# vestibular_vampire.net
KiCad netlist of a schematic drawn in Altium Designer
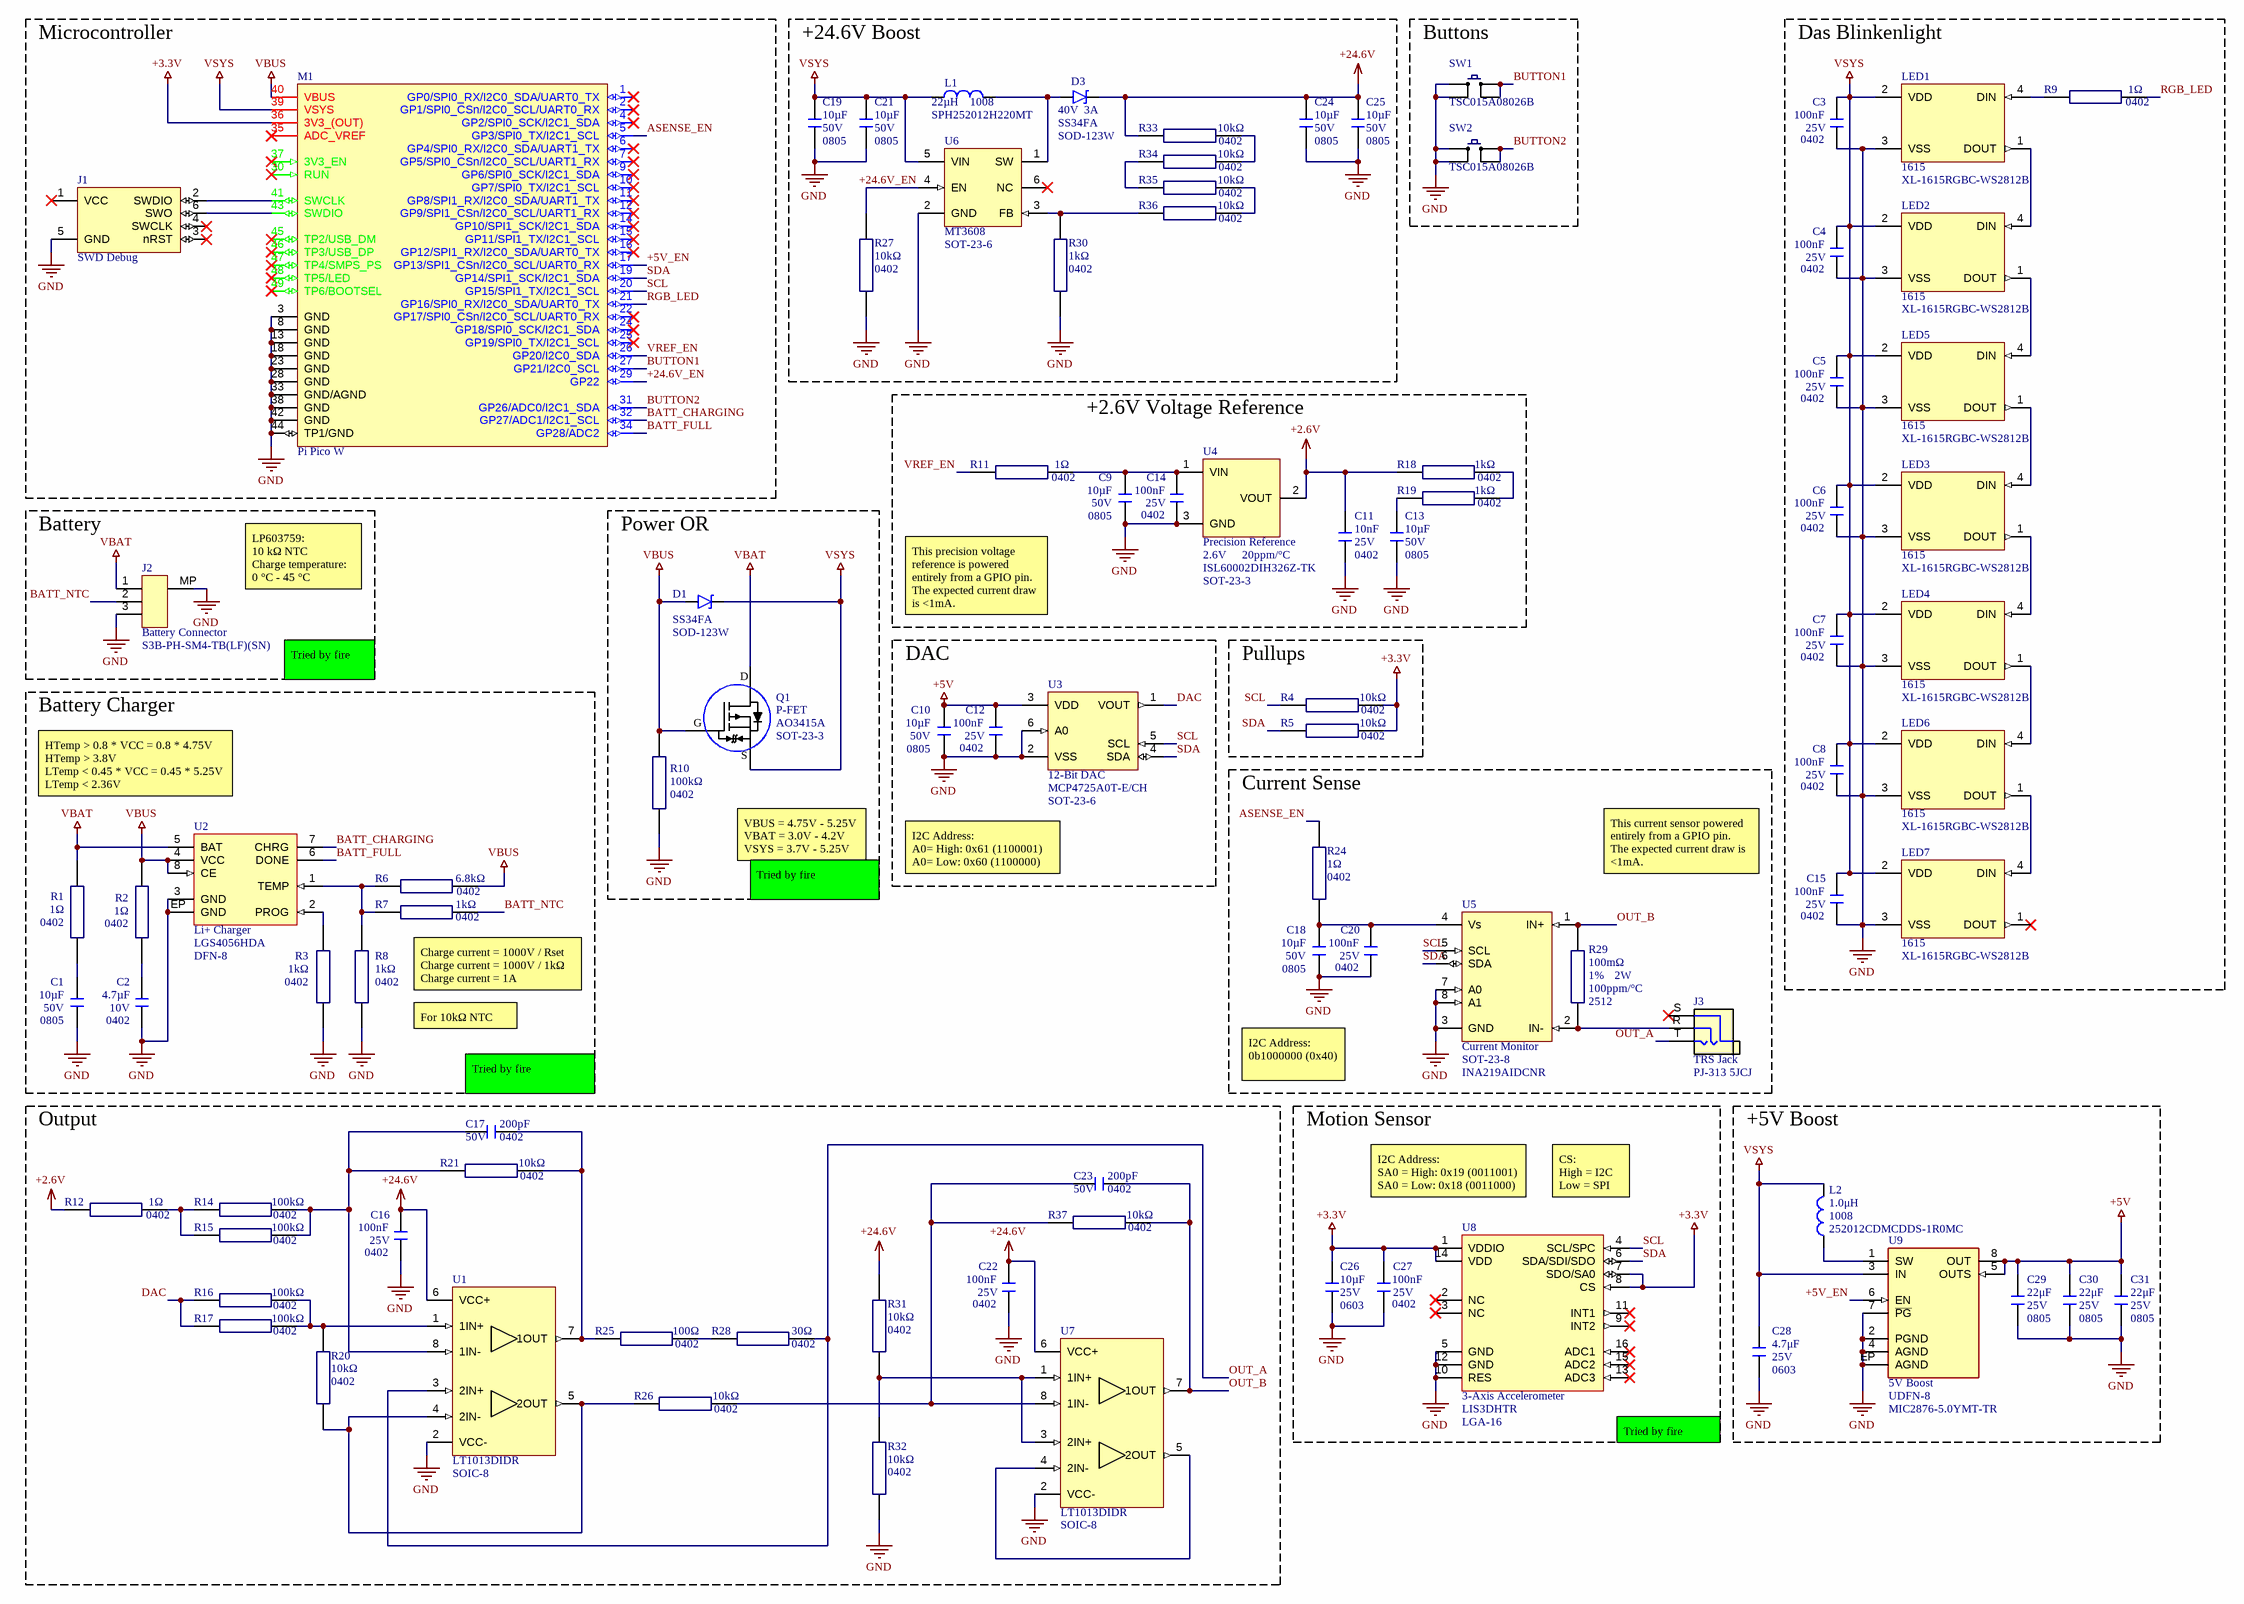
[diagram p0: vestibular_vampire.SchDoc]

(export (version "E")
  (design (tool "Eeschema 10.0.6"))
  (components
    (comp (ref "C1")
      (value "10µF")
      (footprint "0805_capacitor")
      (description "10 μF, 50 V, X5R, 0805 Chip capacitor")
      (fields
        (field (name "MANUFACTURER") "Murata")
        (field (name "MANUFACTURER PART NUMBER") "GRM21BR61H106KE43L")
        (field (name "CASE/PACKAGE") "0805")
        (field (name "VOLTAGE RATING") "50V")
      )
      (libsource (lib "vestibular_vampire") (part "GRM21BR61H106KE43L"))
    )
    (comp (ref "C2")
      (value "4.7µF")
      (footprint "0402_capacitor")
      (description "4.7 µF, 10 V, X5R, 0402 Chip capacitor")
      (fields
        (field (name "MANUFACTURER") "Samsung")
        (field (name "MANUFACTURER PART NUMBER") "CL05A475KP5NRNC")
        (field (name "VOLTAGE RATING") "10V")
        (field (name "CASE/PACKAGE") "0402")
      )
      (libsource (lib "vestibular_vampire") (part "CL05A475KP5NRNC"))
    )
    (comp (ref "C3")
      (value "GRM155R71E104KE14D")
      (footprint "0402_capacitor")
      (description "100 nF, 25 V, X7R, 0402 Chip capacitor")
      (fields
        (field (name "MANUFACTURER") "Murata")
        (field (name "TOLERANCE") "10%")
        (field (name "CASE CODE (IMPERIAL)") "0402")
        (field (name "VOLTAGE") "25V")
        (field (name "CAPACITANCE") "100nF")
      )
      (libsource (lib "vestibular_vampire") (part "GRM155R71E104KE14D"))
    )
    (comp (ref "C4")
      (value "GRM155R71E104KE14D")
      (footprint "0402_capacitor")
      (description "100 nF, 25 V, X7R, 0402 Chip capacitor")
      (fields
        (field (name "MANUFACTURER") "Murata")
        (field (name "TOLERANCE") "10%")
        (field (name "CASE CODE (IMPERIAL)") "0402")
        (field (name "VOLTAGE") "25V")
        (field (name "CAPACITANCE") "100nF")
      )
      (libsource (lib "vestibular_vampire") (part "GRM155R71E104KE14D"))
    )
    (comp (ref "C5")
      (value "GRM155R71E104KE14D")
      (footprint "0402_capacitor")
      (description "100 nF, 25 V, X7R, 0402 Chip capacitor")
      (fields
        (field (name "MANUFACTURER") "Murata")
        (field (name "TOLERANCE") "10%")
        (field (name "CASE CODE (IMPERIAL)") "0402")
        (field (name "VOLTAGE") "25V")
        (field (name "CAPACITANCE") "100nF")
      )
      (libsource (lib "vestibular_vampire") (part "GRM155R71E104KE14D"))
    )
    (comp (ref "C6")
      (value "GRM155R71E104KE14D")
      (footprint "0402_capacitor")
      (description "100 nF, 25 V, X7R, 0402 Chip capacitor")
      (fields
        (field (name "MANUFACTURER") "Murata")
        (field (name "TOLERANCE") "10%")
        (field (name "CASE CODE (IMPERIAL)") "0402")
        (field (name "VOLTAGE") "25V")
        (field (name "CAPACITANCE") "100nF")
      )
      (libsource (lib "vestibular_vampire") (part "GRM155R71E104KE14D"))
    )
    (comp (ref "C7")
      (value "GRM155R71E104KE14D")
      (footprint "0402_capacitor")
      (description "100 nF, 25 V, X7R, 0402 Chip capacitor")
      (fields
        (field (name "MANUFACTURER") "Murata")
        (field (name "TOLERANCE") "10%")
        (field (name "CASE CODE (IMPERIAL)") "0402")
        (field (name "VOLTAGE") "25V")
        (field (name "CAPACITANCE") "100nF")
      )
      (libsource (lib "vestibular_vampire") (part "GRM155R71E104KE14D"))
    )
    (comp (ref "C8")
      (value "GRM155R71E104KE14D")
      (footprint "0402_capacitor")
      (description "100 nF, 25 V, X7R, 0402 Chip capacitor")
      (fields
        (field (name "MANUFACTURER") "Murata")
        (field (name "TOLERANCE") "10%")
        (field (name "CASE CODE (IMPERIAL)") "0402")
        (field (name "VOLTAGE") "25V")
        (field (name "CAPACITANCE") "100nF")
      )
      (libsource (lib "vestibular_vampire") (part "GRM155R71E104KE14D"))
    )
    (comp (ref "C9")
      (value "10µF")
      (footprint "0805_capacitor")
      (description "10 μF, 50 V, X5R, 0805 Chip capacitor")
      (fields
        (field (name "MANUFACTURER") "Murata")
        (field (name "MANUFACTURER PART NUMBER") "GRM21BR61H106KE43L")
        (field (name "CASE/PACKAGE") "0805")
        (field (name "VOLTAGE RATING") "50V")
      )
      (libsource (lib "vestibular_vampire") (part "GRM21BR61H106KE43L"))
    )
    (comp (ref "C10")
      (value "10µF")
      (footprint "0805_capacitor")
      (description "10 μF, 50 V, X5R, 0805 Chip capacitor")
      (fields
        (field (name "MANUFACTURER") "Murata")
        (field (name "MANUFACTURER PART NUMBER") "GRM21BR61H106KE43L")
        (field (name "CASE/PACKAGE") "0805")
        (field (name "VOLTAGE RATING") "50V")
      )
      (libsource (lib "vestibular_vampire") (part "GRM21BR61H106KE43L"))
    )
    (comp (ref "C11")
      (value "CL05B103KA5NNNC")
      (footprint "0402_capacitor")
      (description "10 nF, 25 V, X7R, 0402 Chip capacitor")
      (fields
        (field (name "MANUFACTURER") "Samsung")
        (field (name "TOLERANCE") "10%")
        (field (name "CAPACITANCE") "10nF")
        (field (name "VOLTAGE RATING") "25V")
        (field (name "CASE CODE (IMPERIAL)") "0402")
      )
      (libsource (lib "vestibular_vampire") (part "CL05B103KA5NNNC"))
    )
    (comp (ref "C12")
      (value "GRM155R71E104KE14D")
      (footprint "0402_capacitor")
      (description "100 nF, 25 V, X7R, 0402 Chip capacitor")
      (fields
        (field (name "MANUFACTURER") "Murata")
        (field (name "TOLERANCE") "10%")
        (field (name "CASE CODE (IMPERIAL)") "0402")
        (field (name "VOLTAGE") "25V")
        (field (name "CAPACITANCE") "100nF")
      )
      (libsource (lib "vestibular_vampire") (part "GRM155R71E104KE14D"))
    )
    (comp (ref "C13")
      (value "10µF")
      (footprint "0805_capacitor")
      (description "10 μF, 50 V, X5R, 0805 Chip capacitor")
      (fields
        (field (name "MANUFACTURER") "Murata")
        (field (name "MANUFACTURER PART NUMBER") "GRM21BR61H106KE43L")
        (field (name "CASE/PACKAGE") "0805")
        (field (name "VOLTAGE RATING") "50V")
      )
      (libsource (lib "vestibular_vampire") (part "GRM21BR61H106KE43L"))
    )
    (comp (ref "C14")
      (value "GRM155R71E104KE14D")
      (footprint "0402_capacitor")
      (description "100 nF, 25 V, X7R, 0402 Chip capacitor")
      (fields
        (field (name "MANUFACTURER") "Murata")
        (field (name "TOLERANCE") "10%")
        (field (name "CASE CODE (IMPERIAL)") "0402")
        (field (name "VOLTAGE") "25V")
        (field (name "CAPACITANCE") "100nF")
      )
      (libsource (lib "vestibular_vampire") (part "GRM155R71E104KE14D"))
    )
    (comp (ref "C15")
      (value "GRM155R71E104KE14D")
      (footprint "0402_capacitor")
      (description "100 nF, 25 V, X7R, 0402 Chip capacitor")
      (fields
        (field (name "MANUFACTURER") "Murata")
        (field (name "TOLERANCE") "10%")
        (field (name "CASE CODE (IMPERIAL)") "0402")
        (field (name "VOLTAGE") "25V")
        (field (name "CAPACITANCE") "100nF")
      )
      (libsource (lib "vestibular_vampire") (part "GRM155R71E104KE14D"))
    )
    (comp (ref "C16")
      (value "GRM155R71E104KE14D")
      (footprint "0402_capacitor")
      (description "100 nF, 25 V, X7R, 0402 Chip capacitor")
      (fields
        (field (name "MANUFACTURER") "Murata")
        (field (name "TOLERANCE") "10%")
        (field (name "CASE CODE (IMPERIAL)") "0402")
        (field (name "VOLTAGE") "25V")
        (field (name "CAPACITANCE") "100nF")
      )
      (libsource (lib "vestibular_vampire") (part "GRM155R71E104KE14D"))
    )
    (comp (ref "C17")
      (value "200pF")
      (footprint "0402_capacitor")
      (description "200 pF, 50V, C0G, 0402 Chip capacitor")
      (fields
        (field (name "MANUFACTURER") "Murata")
        (field (name "MANUFACTURER PART NUMBER") "GRT1555C1H201FA02D")
        (field (name "VOLTAGE RATING") "50V")
        (field (name "CASE/PACKAGE") "0402")
      )
      (libsource (lib "vestibular_vampire") (part "GRT1555C1H201FA02D"))
    )
    (comp (ref "C18")
      (value "10µF")
      (footprint "0805_capacitor")
      (description "10 μF, 50 V, X5R, 0805 Chip capacitor")
      (fields
        (field (name "MANUFACTURER") "Murata")
        (field (name "MANUFACTURER PART NUMBER") "GRM21BR61H106KE43L")
        (field (name "CASE/PACKAGE") "0805")
        (field (name "VOLTAGE RATING") "50V")
      )
      (libsource (lib "vestibular_vampire") (part "GRM21BR61H106KE43L"))
    )
    (comp (ref "C19")
      (value "10µF")
      (footprint "0805_capacitor")
      (description "10 μF, 50 V, X5R, 0805 Chip capacitor")
      (fields
        (field (name "MANUFACTURER") "Murata")
        (field (name "MANUFACTURER PART NUMBER") "GRM21BR61H106KE43L")
        (field (name "CASE/PACKAGE") "0805")
        (field (name "VOLTAGE RATING") "50V")
      )
      (libsource (lib "vestibular_vampire") (part "GRM21BR61H106KE43L"))
    )
    (comp (ref "C20")
      (value "GRM155R71E104KE14D")
      (footprint "0402_capacitor")
      (description "100 nF, 25 V, X7R, 0402 Chip capacitor")
      (fields
        (field (name "MANUFACTURER") "Murata")
        (field (name "TOLERANCE") "10%")
        (field (name "CASE CODE (IMPERIAL)") "0402")
        (field (name "VOLTAGE") "25V")
        (field (name "CAPACITANCE") "100nF")
      )
      (libsource (lib "vestibular_vampire") (part "GRM155R71E104KE14D"))
    )
    (comp (ref "C21")
      (value "10µF")
      (footprint "0805_capacitor")
      (description "10 μF, 50 V, X5R, 0805 Chip capacitor")
      (fields
        (field (name "MANUFACTURER") "Murata")
        (field (name "MANUFACTURER PART NUMBER") "GRM21BR61H106KE43L")
        (field (name "CASE/PACKAGE") "0805")
        (field (name "VOLTAGE RATING") "50V")
      )
      (libsource (lib "vestibular_vampire") (part "GRM21BR61H106KE43L"))
    )
    (comp (ref "C22")
      (value "GRM155R71E104KE14D")
      (footprint "0402_capacitor")
      (description "100 nF, 25 V, X7R, 0402 Chip capacitor")
      (fields
        (field (name "MANUFACTURER") "Murata")
        (field (name "TOLERANCE") "10%")
        (field (name "CASE CODE (IMPERIAL)") "0402")
        (field (name "VOLTAGE") "25V")
        (field (name "CAPACITANCE") "100nF")
      )
      (libsource (lib "vestibular_vampire") (part "GRM155R71E104KE14D"))
    )
    (comp (ref "C23")
      (value "200pF")
      (footprint "0402_capacitor")
      (description "200 pF, 50V, C0G, 0402 Chip capacitor")
      (fields
        (field (name "MANUFACTURER") "Murata")
        (field (name "MANUFACTURER PART NUMBER") "GRT1555C1H201FA02D")
        (field (name "VOLTAGE RATING") "50V")
        (field (name "CASE/PACKAGE") "0402")
      )
      (libsource (lib "vestibular_vampire") (part "GRT1555C1H201FA02D"))
    )
    (comp (ref "C24")
      (value "10µF")
      (footprint "0805_capacitor")
      (description "10 μF, 50 V, X5R, 0805 Chip capacitor")
      (fields
        (field (name "MANUFACTURER") "Murata")
        (field (name "MANUFACTURER PART NUMBER") "GRM21BR61H106KE43L")
        (field (name "CASE/PACKAGE") "0805")
        (field (name "VOLTAGE RATING") "50V")
      )
      (libsource (lib "vestibular_vampire") (part "GRM21BR61H106KE43L"))
    )
    (comp (ref "C25")
      (value "10µF")
      (footprint "0805_capacitor")
      (description "10 μF, 50 V, X5R, 0805 Chip capacitor")
      (fields
        (field (name "MANUFACTURER") "Murata")
        (field (name "MANUFACTURER PART NUMBER") "GRM21BR61H106KE43L")
        (field (name "CASE/PACKAGE") "0805")
        (field (name "VOLTAGE RATING") "50V")
      )
      (libsource (lib "vestibular_vampire") (part "GRM21BR61H106KE43L"))
    )
    (comp (ref "C26")
      (value "10µF")
      (footprint "0603_capacitor")
      (description "10 µF, 25 V, X5R, 0603 Chip capacitor")
      (fields
        (field (name "MANUFACTURER") "Samsung")
        (field (name "CASE/PACKAGE") "0603")
        (field (name "TOLERANCE") "20%")
        (field (name "VOLTAGE RATING") "25V")
      )
      (libsource (lib "vestibular_vampire") (part "CL10A106MA8NRNC"))
    )
    (comp (ref "C27")
      (value "GRM155R71E104KE14D")
      (footprint "0402_capacitor")
      (description "100 nF, 25 V, X7R, 0402 Chip capacitor")
      (fields
        (field (name "MANUFACTURER") "Murata")
        (field (name "TOLERANCE") "10%")
        (field (name "CASE CODE (IMPERIAL)") "0402")
        (field (name "VOLTAGE") "25V")
        (field (name "CAPACITANCE") "100nF")
      )
      (libsource (lib "vestibular_vampire") (part "GRM155R71E104KE14D"))
    )
    (comp (ref "C28")
      (value "4.7μF")
      (footprint "0603_capacitor")
      (description "4.7 μF, 25 V, X7R, 0603 Chip capacitor")
      (fields
        (field (name "MANUFACTURER") "TDK")
        (field (name "MANUFACTURER PART NUMBER") "C1608X5R1E475K080AC")
        (field (name "CASE/PACKAGE") "0603")
        (field (name "VOLTAGE RATING") "25V")
      )
      (libsource (lib "vestibular_vampire") (part "C1608X5R1E475K080AC"))
    )
    (comp (ref "C29")
      (value "22μF")
      (footprint "0805_capacitor")
      (description "22 μF, 25 V, X5R, 0805 Chip capacitor")
      (fields
        (field (name "MANUFACTURER") "Murata")
        (field (name "MANUFACTURER PART NUMBER") "GRT21BR61E226ME13L")
        (field (name "RATED DC VOLTAGE (URDC)") "25V")
        (field (name "CASE/PACKAGE") "0805")
      )
      (libsource (lib "vestibular_vampire") (part "GRT21BR61E226ME13L"))
    )
    (comp (ref "C30")
      (value "22μF")
      (footprint "0805_capacitor")
      (description "22 μF, 25 V, X5R, 0805 Chip capacitor")
      (fields
        (field (name "MANUFACTURER") "Murata")
        (field (name "MANUFACTURER PART NUMBER") "GRT21BR61E226ME13L")
        (field (name "RATED DC VOLTAGE (URDC)") "25V")
        (field (name "CASE/PACKAGE") "0805")
      )
      (libsource (lib "vestibular_vampire") (part "GRT21BR61E226ME13L"))
    )
    (comp (ref "C31")
      (value "22μF")
      (footprint "0805_capacitor")
      (description "22 μF, 25 V, X5R, 0805 Chip capacitor")
      (fields
        (field (name "MANUFACTURER") "Murata")
        (field (name "MANUFACTURER PART NUMBER") "GRT21BR61E226ME13L")
        (field (name "RATED DC VOLTAGE (URDC)") "25V")
        (field (name "CASE/PACKAGE") "0805")
      )
      (libsource (lib "vestibular_vampire") (part "GRT21BR61E226ME13L"))
    )
    (comp (ref "D1")
      (value "SS34FA")
      (footprint "SOD-123")
      (description "40 V, 3 A Schottky Rectifier, SOD-123FA")
      (fields
        (field (name "MANUFACTURER") "ON Semiconductor / Fairchild")
        (field (name "MANUFACTURER PART NUMBER") "SS34FA")
        (field (name "HOUSE_PART_NUMBER") "D-SCHOTTKY-3A-SOD123F-002")
        (field (name "CASE/PACKAGE") "SOD-123W")
      )
      (libsource (lib "vestibular_vampire") (part "SS34FA"))
    )
    (comp (ref "D3")
      (value "SS34FA")
      (footprint "SOD-123")
      (description "40 V, 3 A Schottky Rectifier, SOD-123FA")
      (fields
        (field (name "MANUFACTURER") "ON Semiconductor / Fairchild")
        (field (name "MANUFACTURER PART NUMBER") "SS34FA")
        (field (name "AVERAGE RECTIFIED CURRENT") "3A")
        (field (name "MAX REVERSE VOLTAGE (DC)") "40V")
        (field (name "HOUSE_PART_NUMBER") "D-SCHOTTKY-3A-SOD123F-002")
        (field (name "CASE/PACKAGE") "SOD-123W")
      )
      (libsource (lib "vestibular_vampire") (part "SS34FA"))
    )
    (comp (ref "J1")
      (value "SWD Debug")
      (footprint "debug_header_dual")
      (description "Mates with TC-2030-CTX-NL")
      (fields (field (name "HOUSE_PART_NUMBER") "type-value-case-grade"))
      (libsource (lib "vestibular_vampire") (part "TAG_CONN_CTX"))
    )
    (comp (ref "J2")
      (value "Battery Connector")
      (footprint "S3B-PH-SM4-TB")
      (description "3-Pin JST-PH connector, 2mm pitch, right-angle SMD")
      (fields
        (field (name "MANUFACTURER") "JST")
        (field (name "MANUFACTURER PART NUMBER") "S3B-PH-SM4-TB(LF)(SN)")
        (field (name "HOUSE_PART_NUMBER") "S3B-PH-SM4-TB(LF)(SN)")
      )
      (libsource (lib "vestibular_vampire") (part "S3B-PH-SM4-TB(LF)(SN)"))
    )
    (comp (ref "J3")
      (value "TRS Jack")
      (footprint "pj-313_5jcj_3.5mm_trs_jack")
      (description "3.5mm TRS Jack")
      (fields
        (field (name "MANUFACTURER") "SHOU HAN")
        (field (name "MANUFACTURER PART NUMBER") "PJ-313 5JCJ")
      )
      (libsource (lib "vestibular_vampire") (part "PJ-313 5JCJ"))
    )
    (comp (ref "L1")
      (value "22µH")
      (footprint "INDC2520X12N")
      (description "22 μH, .55A, 1008 Inductor")
      (fields
        (field (name "MANUFACTURER") "Sunlord")
        (field (name "CASE/PACKAGE") "1008")
        (field (name "MANUFACTURER PART NUMBER") "SPH252012H220MT")
        (field (name "Comment") "SPH252012H220MT")
      )
      (libsource (lib "vestibular_vampire") (part "SPH252012H220MT"))
    )
    (comp (ref "L2")
      (value "1.0μH")
      (footprint "INDC2520X12N")
      (description "1 μH, 4.2 A, 1008 Inductor")
      (fields
        (field (name "MANUFACTURER") "Sumida")
        (field (name "HOUSE_PART_NUMBER") "L-1uH-1008-002")
        (field (name "PACKAGE") "1008")
        (field (name "MANUFACTURER PART NUMBER") "252012CDMCDDS-1R0MC")
      )
      (libsource (lib "vestibular_vampire") (part "252012CDMCDDS-1R0MC"))
    )
    (comp (ref "LED1")
      (value "WS2812B")
      (footprint "XL-1615RGBC-WS2812B")
      (description "1-wire addressable RGB LED, 1615")
      (fields
        (field (name "MANUFACTURER") "XINGLIGHT")
        (field (name "PACKAGE") "1615")
        (field (name "MANUFACTURER PART NUMBER") "XL-1615RGBC-WS2812B")
      )
      (libsource (lib "vestibular_vampire") (part "XL-1615RGBC-WS2812B"))
    )
    (comp (ref "LED2")
      (value "WS2812B")
      (footprint "XL-1615RGBC-WS2812B")
      (description "1-wire addressable RGB LED, 1615")
      (fields
        (field (name "MANUFACTURER") "XINGLIGHT")
        (field (name "PACKAGE") "1615")
        (field (name "MANUFACTURER PART NUMBER") "XL-1615RGBC-WS2812B")
      )
      (libsource (lib "vestibular_vampire") (part "XL-1615RGBC-WS2812B"))
    )
    (comp (ref "LED3")
      (value "WS2812B")
      (footprint "XL-1615RGBC-WS2812B")
      (description "1-wire addressable RGB LED, 1615")
      (fields
        (field (name "MANUFACTURER") "XINGLIGHT")
        (field (name "PACKAGE") "1615")
        (field (name "MANUFACTURER PART NUMBER") "XL-1615RGBC-WS2812B")
      )
      (libsource (lib "vestibular_vampire") (part "XL-1615RGBC-WS2812B"))
    )
    (comp (ref "LED4")
      (value "WS2812B")
      (footprint "XL-1615RGBC-WS2812B")
      (description "1-wire addressable RGB LED, 1615")
      (fields
        (field (name "MANUFACTURER") "XINGLIGHT")
        (field (name "PACKAGE") "1615")
        (field (name "MANUFACTURER PART NUMBER") "XL-1615RGBC-WS2812B")
      )
      (libsource (lib "vestibular_vampire") (part "XL-1615RGBC-WS2812B"))
    )
    (comp (ref "LED5")
      (value "WS2812B")
      (footprint "XL-1615RGBC-WS2812B")
      (description "1-wire addressable RGB LED, 1615")
      (fields
        (field (name "MANUFACTURER") "XINGLIGHT")
        (field (name "PACKAGE") "1615")
        (field (name "MANUFACTURER PART NUMBER") "XL-1615RGBC-WS2812B")
      )
      (libsource (lib "vestibular_vampire") (part "XL-1615RGBC-WS2812B"))
    )
    (comp (ref "LED6")
      (value "WS2812B")
      (footprint "XL-1615RGBC-WS2812B")
      (description "1-wire addressable RGB LED, 1615")
      (fields
        (field (name "MANUFACTURER") "XINGLIGHT")
        (field (name "PACKAGE") "1615")
        (field (name "MANUFACTURER PART NUMBER") "XL-1615RGBC-WS2812B")
      )
      (libsource (lib "vestibular_vampire") (part "XL-1615RGBC-WS2812B"))
    )
    (comp (ref "LED7")
      (value "WS2812B")
      (footprint "XL-1615RGBC-WS2812B")
      (description "1-wire addressable RGB LED, 1615")
      (fields
        (field (name "MANUFACTURER") "XINGLIGHT")
        (field (name "PACKAGE") "1615")
        (field (name "MANUFACTURER PART NUMBER") "XL-1615RGBC-WS2812B")
      )
      (libsource (lib "vestibular_vampire") (part "XL-1615RGBC-WS2812B"))
    )
    (comp (ref "M1")
      (value "Pi Pico W")
      (footprint "pi_pico_w")
      (fields (field (name "MANUFACTURER") "Raspberry Pi") (field (name "MANUFACTURER PART NUMBER") "SC0918"))
      (libsource (lib "vestibular_vampire") (part "pi_pico_w"))
    )
    (comp (ref "Q1")
      (value "P-FET")
      (footprint "SOT95P280X115-3N")
      (description "P-FET, 30V, 6A, SOT-23-3")
      (fields
        (field (name "MANUFACTURER") "Alpha & Omega Semiconductor")
        (field (name "CASE/PACKAGE") "SOT-23-3")
        (field (name "MANUFACTURER PART NUMBER") "AO3415A")
        (field (name "HOUSE_PART_NUMBER") "AO3415A")
      )
      (libsource (lib "vestibular_vampire") (part "AO3415A"))
    )
    (comp (ref "R1")
      (value "1Ω")
      (footprint "0402_resistor")
      (description "1 Ω, 0402 Chip resistor")
      (fields
        (field (name "MANUFACTURER") "Uniroyal")
        (field (name "MANUFACTURER PART NUMBER") "0402WGF100KTCE")
        (field (name "CASE/PACKAGE") "0402")
      )
      (libsource (lib "vestibular_vampire") (part "0402WGF100KTCE"))
    )
    (comp (ref "R2")
      (value "1Ω")
      (footprint "0402_resistor")
      (description "1 Ω, 0402 Chip resistor")
      (fields
        (field (name "MANUFACTURER") "Uniroyal")
        (field (name "MANUFACTURER PART NUMBER") "0402WGF100KTCE")
        (field (name "CASE/PACKAGE") "0402")
      )
      (libsource (lib "vestibular_vampire") (part "0402WGF100KTCE"))
    )
    (comp (ref "R3")
      (value "1kΩ")
      (footprint "0402_resistor")
      (description "1 kΩ, 0402 Chip resistor")
      (fields
        (field (name "MANUFACTURER") "Yageo")
        (field (name "MANUFACTURER PART NUMBER") "RC0402JR-071KL")
        (field (name "CASE/PACKAGE") "0402")
      )
      (libsource (lib "vestibular_vampire") (part "RC0402JR-071KL"))
    )
    (comp (ref "R4")
      (value "10kΩ")
      (footprint "0402_resistor")
      (description "10 kΩ, 0402 Chip resistor")
      (fields
        (field (name "MANUFACTURER") "Yageo")
        (field (name "MANUFACTURER PART NUMBER") "RC0402FR-0710KL")
        (field (name "CASE CODE (IMPERIAL)") "0402")
      )
      (libsource (lib "vestibular_vampire") (part "RC0402FR-0710KL"))
    )
    (comp (ref "R5")
      (value "10kΩ")
      (footprint "0402_resistor")
      (description "10 kΩ, 0402 Chip resistor")
      (fields
        (field (name "MANUFACTURER") "Yageo")
        (field (name "MANUFACTURER PART NUMBER") "RC0402FR-0710KL")
        (field (name "CASE CODE (IMPERIAL)") "0402")
      )
      (libsource (lib "vestibular_vampire") (part "RC0402FR-0710KL"))
    )
    (comp (ref "R6")
      (value "6.8kΩ")
      (footprint "0402_resistor")
      (description "6.8 kΩ, 0402 Chip resistor")
      (fields
        (field (name "MANUFACTURER") "Yageo")
        (field (name "MANUFACTURER PART NUMBER") "RC0402FR-076K8L")
        (field (name "CASE/PACKAGE") "0402")
      )
      (libsource (lib "vestibular_vampire") (part "RC0402FR-076K8L"))
    )
    (comp (ref "R7")
      (value "1kΩ")
      (footprint "0402_resistor")
      (description "1 kΩ, 0402 Chip resistor")
      (fields
        (field (name "MANUFACTURER") "Yageo")
        (field (name "MANUFACTURER PART NUMBER") "RC0402JR-071KL")
        (field (name "CASE/PACKAGE") "0402")
      )
      (libsource (lib "vestibular_vampire") (part "RC0402JR-071KL"))
    )
    (comp (ref "R8")
      (value "1kΩ")
      (footprint "0402_resistor")
      (description "1 kΩ, 0402 Chip resistor")
      (fields
        (field (name "MANUFACTURER") "Yageo")
        (field (name "MANUFACTURER PART NUMBER") "RC0402JR-071KL")
        (field (name "CASE/PACKAGE") "0402")
      )
      (libsource (lib "vestibular_vampire") (part "RC0402JR-071KL"))
    )
    (comp (ref "R9")
      (value "1Ω")
      (footprint "0402_resistor")
      (description "1 Ω, 0402 Chip resistor")
      (fields
        (field (name "MANUFACTURER") "Uniroyal")
        (field (name "MANUFACTURER PART NUMBER") "0402WGF100KTCE")
        (field (name "CASE/PACKAGE") "0402")
      )
      (libsource (lib "vestibular_vampire") (part "0402WGF100KTCE"))
    )
    (comp (ref "R10")
      (value "100kΩ")
      (footprint "0402_resistor")
      (description "100 kΩ, 0402 Chip resistor")
      (fields
        (field (name "MANUFACTURER") "Yageo")
        (field (name "MANUFACTURER PART NUMBER") "RC0402FR-07100KL")
        (field (name "CASE/PACKAGE") "0402")
      )
      (libsource (lib "vestibular_vampire") (part "RC0402FR-07100KL"))
    )
    (comp (ref "R11")
      (value "1Ω")
      (footprint "0402_resistor")
      (description "1 Ω, 0402 Chip resistor")
      (fields
        (field (name "MANUFACTURER") "Uniroyal")
        (field (name "MANUFACTURER PART NUMBER") "0402WGF100KTCE")
        (field (name "CASE/PACKAGE") "0402")
      )
      (libsource (lib "vestibular_vampire") (part "0402WGF100KTCE"))
    )
    (comp (ref "R12")
      (value "1Ω")
      (footprint "0402_resistor")
      (description "1 Ω, 0402 Chip resistor")
      (fields
        (field (name "MANUFACTURER") "Uniroyal")
        (field (name "MANUFACTURER PART NUMBER") "0402WGF100KTCE")
        (field (name "CASE/PACKAGE") "0402")
      )
      (libsource (lib "vestibular_vampire") (part "0402WGF100KTCE"))
    )
    (comp (ref "R14")
      (value "100kΩ")
      (footprint "0402_resistor")
      (description "100 kΩ, 0402 Chip resistor")
      (fields
        (field (name "MANUFACTURER") "Yageo")
        (field (name "MANUFACTURER PART NUMBER") "RC0402FR-07100KL")
        (field (name "CASE/PACKAGE") "0402")
      )
      (libsource (lib "vestibular_vampire") (part "RC0402FR-07100KL"))
    )
    (comp (ref "R15")
      (value "100kΩ")
      (footprint "0402_resistor")
      (description "100 kΩ, 0402 Chip resistor")
      (fields
        (field (name "MANUFACTURER") "Yageo")
        (field (name "MANUFACTURER PART NUMBER") "RC0402FR-07100KL")
        (field (name "CASE/PACKAGE") "0402")
      )
      (libsource (lib "vestibular_vampire") (part "RC0402FR-07100KL"))
    )
    (comp (ref "R16")
      (value "100kΩ")
      (footprint "0402_resistor")
      (description "100 kΩ, 0402 Chip resistor")
      (fields
        (field (name "MANUFACTURER") "Yageo")
        (field (name "MANUFACTURER PART NUMBER") "RC0402FR-07100KL")
        (field (name "CASE/PACKAGE") "0402")
      )
      (libsource (lib "vestibular_vampire") (part "RC0402FR-07100KL"))
    )
    (comp (ref "R17")
      (value "100kΩ")
      (footprint "0402_resistor")
      (description "100 kΩ, 0402 Chip resistor")
      (fields
        (field (name "MANUFACTURER") "Yageo")
        (field (name "MANUFACTURER PART NUMBER") "RC0402FR-07100KL")
        (field (name "CASE/PACKAGE") "0402")
      )
      (libsource (lib "vestibular_vampire") (part "RC0402FR-07100KL"))
    )
    (comp (ref "R18")
      (value "1kΩ")
      (footprint "0402_resistor")
      (description "1 kΩ, 0402 Chip resistor")
      (fields
        (field (name "MANUFACTURER") "Yageo")
        (field (name "MANUFACTURER PART NUMBER") "RC0402JR-071KL")
        (field (name "CASE/PACKAGE") "0402")
      )
      (libsource (lib "vestibular_vampire") (part "RC0402JR-071KL"))
    )
    (comp (ref "R19")
      (value "1kΩ")
      (footprint "0402_resistor")
      (description "1 kΩ, 0402 Chip resistor")
      (fields
        (field (name "MANUFACTURER") "Yageo")
        (field (name "MANUFACTURER PART NUMBER") "RC0402JR-071KL")
        (field (name "CASE/PACKAGE") "0402")
      )
      (libsource (lib "vestibular_vampire") (part "RC0402JR-071KL"))
    )
    (comp (ref "R20")
      (value "10kΩ")
      (footprint "0402_resistor")
      (description "10 kΩ, 0402 Chip resistor")
      (fields
        (field (name "MANUFACTURER") "Yageo")
        (field (name "MANUFACTURER PART NUMBER") "RC0402FR-0710KL")
        (field (name "CASE CODE (IMPERIAL)") "0402")
      )
      (libsource (lib "vestibular_vampire") (part "RC0402FR-0710KL"))
    )
    (comp (ref "R21")
      (value "10kΩ")
      (footprint "0402_resistor")
      (description "10 kΩ, 0402 Chip resistor")
      (fields
        (field (name "MANUFACTURER") "Yageo")
        (field (name "MANUFACTURER PART NUMBER") "RC0402FR-0710KL")
        (field (name "CASE CODE (IMPERIAL)") "0402")
      )
      (libsource (lib "vestibular_vampire") (part "RC0402FR-0710KL"))
    )
    (comp (ref "R24")
      (value "1Ω")
      (footprint "0402_resistor")
      (description "1 Ω, 0402 Chip resistor")
      (fields
        (field (name "MANUFACTURER") "Uniroyal")
        (field (name "MANUFACTURER PART NUMBER") "0402WGF100KTCE")
        (field (name "CASE/PACKAGE") "0402")
      )
      (libsource (lib "vestibular_vampire") (part "0402WGF100KTCE"))
    )
    (comp (ref "R25")
      (value "RMCF0402FT100R")
      (footprint "0402_resistor")
      (description "100 Ω, 0402 Chip resistor")
      (fields
        (field (name "MANUFACTURER") "Stackpole Electronics")
        (field (name "TOLERANCE") "1%")
        (field (name "CASE CODE (IMPERIAL)") "0402")
        (field (name "RESISTANCE") "100Ω")
      )
      (libsource (lib "vestibular_vampire") (part "RMCF0402FT100R"))
    )
    (comp (ref "R26")
      (value "10kΩ")
      (footprint "0402_resistor")
      (description "10 kΩ, 0402 Chip resistor")
      (fields
        (field (name "MANUFACTURER") "Yageo")
        (field (name "MANUFACTURER PART NUMBER") "RC0402FR-0710KL")
        (field (name "CASE CODE (IMPERIAL)") "0402")
      )
      (libsource (lib "vestibular_vampire") (part "RC0402FR-0710KL"))
    )
    (comp (ref "R27")
      (value "10kΩ")
      (footprint "0402_resistor")
      (description "10 kΩ, 0402 Chip resistor")
      (fields
        (field (name "MANUFACTURER") "Yageo")
        (field (name "MANUFACTURER PART NUMBER") "RC0402FR-0710KL")
        (field (name "CASE CODE (IMPERIAL)") "0402")
      )
      (libsource (lib "vestibular_vampire") (part "RC0402FR-0710KL"))
    )
    (comp (ref "R28")
      (value "30Ω")
      (footprint "0402_resistor")
      (description "30 Ω, 1%, 0402 Chip resistor")
      (fields
        (field (name "MANUFACTURER") "Yageo Group")
        (field (name "MANUFACTURER PART NUMBER") "RC0402FR-0730RL")
        (field (name "CASE/PACKAGE") "0402")
      )
      (libsource (lib "vestibular_vampire") (part "RC0402FR-0730RL"))
    )
    (comp (ref "R29")
      (value "100mΩ")
      (footprint "2512_resistor")
      (description "100 mΩ, 1%, 100ppm/℃, 2W, 2512 Chip Resistor")
      (fields
        (field (name "MANUFACTURER") "Yageo Group")
        (field (name "MANUFACTURER PART NUMBER") "PT2512FK-7W0R1L")
        (field (name "CASE/PACKAGE") "2512")
        (field (name "TOLERANCE") "1%")
        (field (name "TEMPERATURE COEFFICIENT") "100ppm/°C")
        (field (name "POWER DISSIPATION") "2W")
      )
      (libsource (lib "vestibular_vampire") (part "PT2512FK-7W0R1L"))
    )
    (comp (ref "R30")
      (value "1kΩ")
      (footprint "0402_resistor")
      (description "1 kΩ, 0402 Chip resistor")
      (fields
        (field (name "MANUFACTURER") "Yageo")
        (field (name "MANUFACTURER PART NUMBER") "RC0402JR-071KL")
        (field (name "CASE/PACKAGE") "0402")
      )
      (libsource (lib "vestibular_vampire") (part "RC0402JR-071KL"))
    )
    (comp (ref "R31")
      (value "10kΩ")
      (footprint "0402_resistor")
      (description "10 kΩ, 0402 Chip resistor")
      (fields
        (field (name "MANUFACTURER") "Yageo")
        (field (name "MANUFACTURER PART NUMBER") "RC0402FR-0710KL")
        (field (name "CASE CODE (IMPERIAL)") "0402")
      )
      (libsource (lib "vestibular_vampire") (part "RC0402FR-0710KL"))
    )
    (comp (ref "R32")
      (value "10kΩ")
      (footprint "0402_resistor")
      (description "10 kΩ, 0402 Chip resistor")
      (fields
        (field (name "MANUFACTURER") "Yageo")
        (field (name "MANUFACTURER PART NUMBER") "RC0402FR-0710KL")
        (field (name "CASE CODE (IMPERIAL)") "0402")
      )
      (libsource (lib "vestibular_vampire") (part "RC0402FR-0710KL"))
    )
    (comp (ref "R33")
      (value "10kΩ")
      (footprint "0402_resistor")
      (description "10 kΩ, 0402 Chip resistor")
      (fields
        (field (name "MANUFACTURER") "Yageo")
        (field (name "MANUFACTURER PART NUMBER") "RC0402FR-0710KL")
        (field (name "CASE CODE (IMPERIAL)") "0402")
      )
      (libsource (lib "vestibular_vampire") (part "RC0402FR-0710KL"))
    )
    (comp (ref "R34")
      (value "10kΩ")
      (footprint "0402_resistor")
      (description "10 kΩ, 0402 Chip resistor")
      (fields
        (field (name "MANUFACTURER") "Yageo")
        (field (name "MANUFACTURER PART NUMBER") "RC0402FR-0710KL")
        (field (name "CASE CODE (IMPERIAL)") "0402")
      )
      (libsource (lib "vestibular_vampire") (part "RC0402FR-0710KL"))
    )
    (comp (ref "R35")
      (value "10kΩ")
      (footprint "0402_resistor")
      (description "10 kΩ, 0402 Chip resistor")
      (fields
        (field (name "MANUFACTURER") "Yageo")
        (field (name "MANUFACTURER PART NUMBER") "RC0402FR-0710KL")
        (field (name "CASE CODE (IMPERIAL)") "0402")
      )
      (libsource (lib "vestibular_vampire") (part "RC0402FR-0710KL"))
    )
    (comp (ref "R36")
      (value "10kΩ")
      (footprint "0402_resistor")
      (description "10 kΩ, 0402 Chip resistor")
      (fields
        (field (name "MANUFACTURER") "Yageo")
        (field (name "MANUFACTURER PART NUMBER") "RC0402FR-0710KL")
        (field (name "CASE CODE (IMPERIAL)") "0402")
      )
      (libsource (lib "vestibular_vampire") (part "RC0402FR-0710KL"))
    )
    (comp (ref "R37")
      (value "10kΩ")
      (footprint "0402_resistor")
      (description "10 kΩ, 0402 Chip resistor")
      (fields
        (field (name "MANUFACTURER") "Yageo")
        (field (name "MANUFACTURER PART NUMBER") "RC0402FR-0710KL")
        (field (name "CASE CODE (IMPERIAL)") "0402")
      )
      (libsource (lib "vestibular_vampire") (part "RC0402FR-0710KL"))
    )
    (comp (ref "SW1")
      (value "TSC015A08026B")
      (footprint "TSC015A08026B")
      (description "Tactile switch, SPST")
      (fields
        (field (name "HOUSE_PART_NUMBER") "SW-TAC-4.5-8-260gf")
        (field (name "MANUFACTURER PART NUMBER") "TSC015A08026B")
      )
      (libsource (lib "vestibular_vampire") (part "TSC015A08026B"))
    )
    (comp (ref "SW2")
      (value "TSC015A08026B")
      (footprint "TSC015A08026B")
      (description "Tactile switch, SPST")
      (fields
        (field (name "HOUSE_PART_NUMBER") "SW-TAC-4.5-8-260gf")
        (field (name "MANUFACTURER PART NUMBER") "TSC015A08026B")
      )
      (libsource (lib "vestibular_vampire") (part "TSC015A08026B"))
    )
    (comp (ref "U1")
      (value "LT1013DIDR")
      (footprint "SOIC127P600X175-8N")
      (description "Op-Amp, 5-44 V, SOIC-8")
      (fields
        (field (name "MANUFACTURER") "Texas Instruments")
        (field (name "MANUFACTURER PART NUMBER") "LT1013DIDR")
        (field (name "CASE/PACKAGE") "SOIC-8")
      )
      (libsource (lib "vestibular_vampire") (part "LT1013DIDR"))
    )
    (comp (ref "U2")
      (value "Li+ Charger")
      (footprint "SON50P200X80_HS-9N")
      (description "Battery Charger, DFN-8(2x2)")
      (fields
        (field (name "MANUFACTURER PART NUMBER") "LGS4056HDA")
        (field (name "PACKAGE") "DFN-8")
        (field (name "HOUSE_PART_NUMBER") "LGS4056HDA")
      )
      (libsource (lib "vestibular_vampire") (part "LGS4056H"))
    )
    (comp (ref "U3")
      (value "12-Bit DAC")
      (footprint "SOT95P280X110-6N")
      (description "DAC, 12-bit, SOT-23-6")
      (fields
        (field (name "MANUFACTURER") "Microchip")
        (field (name "CASE/PACKAGE") "SOT-23-6")
        (field (name "MANUFACTURER PART NUMBER") "MCP4725A0T-E/CH")
      )
      (libsource (lib "vestibular_vampire") (part "MCP4725A0T-E/CH"))
    )
    (comp (ref "U4")
      (value "Precision Reference")
      (footprint "SOT95P280X115-3N")
      (description "2.6 V, ±5.0mV, 20ppm/°C, 7 mA Precision Voltage Reference, SOT-23-3")
      (fields
        (field (name "MANUFACTURER") "Renesas")
        (field (name "TOLERANCE") "0.19%")
        (field (name "CASE/PACKAGE") "SOT-23-3")
        (field (name "TEMPERATURE COEFFICIENT") "20ppm/°C")
        (field (name "REFERENCE VOLTAGE") "2.6V")
        (field (name "MANUFACTURER PART NUMBER") "ISL60002DIH326Z-TK")
      )
      (libsource (lib "vestibular_vampire") (part "ISL60002DIH326Z-TK"))
    )
    (comp (ref "U5")
      (value "Current Monitor")
      (footprint "SOT-23-8")
      (description "12-bit, 26 V, Current monitor, SOT-23-8")
      (fields
        (field (name "MANUFACTURER") "Texas Instruments")
        (field (name "CASE/PACKAGE") "SOT-23-8")
        (field (name "MANUFACTURER PART NUMBER") "INA219AIDCNR")
      )
      (libsource (lib "vestibular_vampire") (part "INA219AIDCNR"))
    )
    (comp (ref "U6")
      (value "MT3608")
      (footprint "SOT95P280X110-6N")
      (description "Boost converter, 2A, SOT-23-6")
      (fields (field (name "MANUFACTURER PART NUMBER") "MT3608") (field (name "PACKAGE") "SOT-23-6"))
      (libsource (lib "vestibular_vampire") (part "MT3608"))
    )
    (comp (ref "U7")
      (value "LT1013DIDR")
      (footprint "SOIC127P600X175-8N")
      (description "Op-Amp, 5-44 V, SOIC-8")
      (fields
        (field (name "MANUFACTURER") "Texas Instruments")
        (field (name "MANUFACTURER PART NUMBER") "LT1013DIDR")
        (field (name "CASE/PACKAGE") "SOIC-8")
      )
      (libsource (lib "vestibular_vampire") (part "LT1013DIDR"))
    )
    (comp (ref "U8")
      (value "3-Axis Accelerometer")
      (footprint "LGA50P300X300X100-16N")
      (description "3-Axis accelerometer, 16-bit, I2C/SPI, LGA-16")
      (fields
        (field (name "MANUFACTURER") "STMicroelectronics")
        (field (name "CASE/PACKAGE") "LGA-16")
        (field (name "MANUFACTURER PART NUMBER") "LIS3DHTR")
        (field (name "HOUSE_PART_NUMBER") "LIS3DHTR")
      )
      (libsource (lib "vestibular_vampire") (part "LIS3DHTR"))
    )
    (comp (ref "U9")
      (value "5V Boost")
      (footprint "SON50P200X50_HS-9N")
      (description "5V Synchronous Boost, UDFN-8")
      (fields
        (field (name "MANUFACTURER") "Microchip")
        (field (name "CASE/PACKAGE") "UDFN-8")
        (field (name "MANUFACTURER PART NUMBER") "MIC2876-5.0YMT-TR")
      )
      (libsource (lib "vestibular_vampire") (part "MIC2876-5.0YMT-TR"))
    )
  )
  (nets
    (net (code "1") (name "+2.6V") (class "Default")
      (node (ref "C11") (pin "2") (pinfunction "2_2") (pintype "passive"))
      (node (ref "R12") (pin "2") (pinfunction "2_2") (pintype "passive"))
      (node (ref "R18") (pin "2") (pinfunction "2_2") (pintype "passive"))
      (node (ref "U4") (pin "2") (pinfunction "VOUT_2") (pintype "power_in"))
    )
    (net (code "2") (name "+3.3V") (class "Default")
      (node (ref "C26") (pin "2") (pinfunction "2_2") (pintype "passive"))
      (node (ref "C27") (pin "2") (pinfunction "2_2") (pintype "passive"))
      (node (ref "M1") (pin "36") (pinfunction "3V3_(OUT)_36") (pintype "power_in"))
      (node (ref "R4") (pin "2") (pinfunction "2_2") (pintype "passive"))
      (node (ref "R5") (pin "2") (pinfunction "2_2") (pintype "passive"))
      (node (ref "U8") (pin "1") (pinfunction "VDDIO_1") (pintype "power_in"))
      (node (ref "U8") (pin "14") (pinfunction "VDD_14") (pintype "power_in"))
      (node (ref "U8") (pin "7") (pinfunction "SDO/SA0_7") (pintype "bidirectional"))
      (node (ref "U8") (pin "8") (pinfunction "CS_8") (pintype "input"))
    )
    (net (code "3") (name "+5V") (class "Default")
      (node (ref "C10") (pin "2") (pinfunction "2_2") (pintype "passive"))
      (node (ref "C12") (pin "2") (pinfunction "2_2") (pintype "passive"))
      (node (ref "C29") (pin "2") (pinfunction "2_2") (pintype "passive"))
      (node (ref "C30") (pin "2") (pinfunction "2_2") (pintype "passive"))
      (node (ref "C31") (pin "2") (pinfunction "2_2") (pintype "passive"))
      (node (ref "U3") (pin "3") (pinfunction "VDD_3") (pintype "power_in"))
      (node (ref "U9") (pin "5") (pinfunction "OUTS_5") (pintype "input"))
      (node (ref "U9") (pin "8") (pinfunction "OUT_8") (pintype "power_in"))
    )
    (net (code "4") (name "+24.6V") (class "Default")
      (node (ref "C16") (pin "2") (pinfunction "2_2") (pintype "passive"))
      (node (ref "C22") (pin "2") (pinfunction "2_2") (pintype "passive"))
      (node (ref "C24") (pin "2") (pinfunction "2_2") (pintype "passive"))
      (node (ref "C25") (pin "2") (pinfunction "2_2") (pintype "passive"))
      (node (ref "D3") (pin "K") (pinfunction "K_K") (pintype "passive"))
      (node (ref "R31") (pin "1") (pinfunction "1_1") (pintype "passive"))
      (node (ref "R33") (pin "1") (pinfunction "1_1") (pintype "passive"))
      (node (ref "U1") (pin "6") (pinfunction "VCC+_6") (pintype "power_in"))
      (node (ref "U7") (pin "6") (pinfunction "VCC+_6") (pintype "power_in"))
    )
    (net (code "5") (name "/+5V_EN") (class "Default")
      (node (ref "M1") (pin "17") (pinfunction "GP13/SPI1_CSn/I2C0_SCL/UART0_RX_17") (pintype "bidirectional"))
      (node (ref "U9") (pin "6") (pinfunction "EN_6") (pintype "input"))
    )
    (net (code "6") (name "/+24.6V_EN") (class "Default")
      (node (ref "M1") (pin "29") (pinfunction "GP22_29") (pintype "bidirectional"))
      (node (ref "R27") (pin "1") (pinfunction "1_1") (pintype "passive"))
      (node (ref "U6") (pin "4") (pinfunction "EN_4") (pintype "input"))
    )
    (net (code "7") (name "/ASENSE_EN") (class "Default")
      (node (ref "M1") (pin "5") (pinfunction "GP3/SPI0_TX/I2C1_SCL_5") (pintype "bidirectional"))
      (node (ref "R24") (pin "2") (pinfunction "2_2") (pintype "passive"))
    )
    (net (code "8") (name "/BATT_CHARGING") (class "Default")
      (node (ref "M1") (pin "32") (pinfunction "GP27/ADC1/I2C1_SCL_32") (pintype "bidirectional"))
      (node (ref "U2") (pin "7") (pinfunction "CHRG_7") (pintype "open_collector"))
    )
    (net (code "9") (name "/BATT_FULL") (class "Default")
      (node (ref "M1") (pin "34") (pinfunction "GP28/ADC2_34") (pintype "bidirectional"))
      (node (ref "U2") (pin "6") (pinfunction "DONE_6") (pintype "open_collector"))
    )
    (net (code "10") (name "/BATT_NTC") (class "Default")
      (node (ref "J2") (pin "2") (pintype "passive"))
      (node (ref "R7") (pin "1") (pinfunction "1_1") (pintype "passive"))
    )
    (net (code "11") (name "/BUTTON1") (class "Default")
      (node (ref "M1") (pin "27") (pinfunction "GP21/I2C0_SCL_27") (pintype "bidirectional"))
      (node (ref "SW1") (pin "3") (pinfunction "3_3") (pintype "passive"))
      (node (ref "SW1") (pin "4") (pinfunction "4_4") (pintype "passive"))
    )
    (net (code "12") (name "/BUTTON2") (class "Default")
      (node (ref "M1") (pin "31") (pinfunction "GP26/ADC0/I2C1_SDA_31") (pintype "bidirectional"))
      (node (ref "SW2") (pin "3") (pinfunction "3_3") (pintype "passive"))
      (node (ref "SW2") (pin "4") (pinfunction "4_4") (pintype "passive"))
    )
    (net (code "13") (name "/DAC") (class "Default")
      (node (ref "R16") (pin "2") (pinfunction "2_2") (pintype "passive"))
      (node (ref "R17") (pin "2") (pinfunction "2_2") (pintype "passive"))
      (node (ref "U3") (pin "1") (pinfunction "VOUT_1") (pintype "output"))
    )
    (net (code "14") (name "/OUT_A") (class "Default")
      (node (ref "J3") (pin "T") (pinfunction "T_T") (pintype "passive"))
      (node (ref "R28") (pin "2") (pinfunction "2_2") (pintype "passive"))
      (node (ref "U1") (pin "3") (pinfunction "2IN+_3") (pintype "input"))
    )
    (net (code "15") (name "/OUT_B") (class "Default")
      (node (ref "C23") (pin "2") (pinfunction "2_2") (pintype "passive"))
      (node (ref "R29") (pin "1") (pinfunction "1_1") (pintype "passive"))
      (node (ref "R37") (pin "2") (pinfunction "2_2") (pintype "passive"))
      (node (ref "U5") (pin "1") (pinfunction "IN+_1") (pintype "input"))
      (node (ref "U7") (pin "7") (pinfunction "1OUT_7") (pintype "output"))
    )
    (net (code "16") (name "/RGB_LED") (class "Default")
      (node (ref "M1") (pin "21") (pinfunction "GP16/SPI0_RX/I2C0_SDA/UART0_TX_21") (pintype "bidirectional"))
      (node (ref "R9") (pin "1") (pinfunction "1_1") (pintype "passive"))
    )
    (net (code "17") (name "/SCL") (class "Default")
      (node (ref "M1") (pin "20") (pinfunction "GP15/SPI1_TX/I2C1_SCL_20") (pintype "bidirectional"))
      (node (ref "R4") (pin "1") (pinfunction "1_1") (pintype "passive"))
      (node (ref "U3") (pin "5") (pinfunction "SCL_5") (pintype "input"))
      (node (ref "U5") (pin "5") (pinfunction "SCL_5") (pintype "input"))
      (node (ref "U8") (pin "4") (pinfunction "SCL/SPC_4") (pintype "input"))
    )
    (net (code "18") (name "/SDA") (class "Default")
      (node (ref "M1") (pin "19") (pinfunction "GP14/SPI1_SCK/I2C1_SDA_19") (pintype "bidirectional"))
      (node (ref "R5") (pin "1") (pinfunction "1_1") (pintype "passive"))
      (node (ref "U3") (pin "4") (pinfunction "SDA_4") (pintype "bidirectional"))
      (node (ref "U5") (pin "6") (pinfunction "SDA_6") (pintype "bidirectional"))
      (node (ref "U8") (pin "6") (pinfunction "SDA/SDI/SDO_6") (pintype "bidirectional"))
    )
    (net (code "19") (name "/VREF_EN") (class "Default")
      (node (ref "M1") (pin "26") (pinfunction "GP20/I2C0_SDA_26") (pintype "bidirectional"))
      (node (ref "R11") (pin "2") (pinfunction "2_2") (pintype "passive"))
    )
    (net (code "20") (name "GND") (class "Default")
      (node (ref "C1") (pin "1") (pinfunction "1_1") (pintype "passive"))
      (node (ref "C10") (pin "1") (pinfunction "1_1") (pintype "passive"))
      (node (ref "C11") (pin "1") (pinfunction "1_1") (pintype "passive"))
      (node (ref "C12") (pin "1") (pinfunction "1_1") (pintype "passive"))
      (node (ref "C13") (pin "1") (pinfunction "1_1") (pintype "passive"))
      (node (ref "C14") (pin "1") (pinfunction "1_1") (pintype "passive"))
      (node (ref "C15") (pin "1") (pinfunction "1_1") (pintype "passive"))
      (node (ref "C16") (pin "1") (pinfunction "1_1") (pintype "passive"))
      (node (ref "C18") (pin "1") (pinfunction "1_1") (pintype "passive"))
      (node (ref "C19") (pin "1") (pinfunction "1_1") (pintype "passive"))
      (node (ref "C2") (pin "1") (pinfunction "1_1") (pintype "passive"))
      (node (ref "C20") (pin "1") (pinfunction "1_1") (pintype "passive"))
      (node (ref "C21") (pin "1") (pinfunction "1_1") (pintype "passive"))
      (node (ref "C22") (pin "1") (pinfunction "1_1") (pintype "passive"))
      (node (ref "C24") (pin "1") (pinfunction "1_1") (pintype "passive"))
      (node (ref "C25") (pin "1") (pinfunction "1_1") (pintype "passive"))
      (node (ref "C26") (pin "1") (pinfunction "1_1") (pintype "passive"))
      (node (ref "C27") (pin "1") (pinfunction "1_1") (pintype "passive"))
      (node (ref "C28") (pin "1") (pinfunction "1_1") (pintype "passive"))
      (node (ref "C29") (pin "1") (pinfunction "1_1") (pintype "passive"))
      (node (ref "C3") (pin "1") (pinfunction "1_1") (pintype "passive"))
      (node (ref "C30") (pin "1") (pinfunction "1_1") (pintype "passive"))
      (node (ref "C31") (pin "1") (pinfunction "1_1") (pintype "passive"))
      (node (ref "C4") (pin "1") (pinfunction "1_1") (pintype "passive"))
      (node (ref "C5") (pin "1") (pinfunction "1_1") (pintype "passive"))
      (node (ref "C6") (pin "1") (pinfunction "1_1") (pintype "passive"))
      (node (ref "C7") (pin "1") (pinfunction "1_1") (pintype "passive"))
      (node (ref "C8") (pin "1") (pinfunction "1_1") (pintype "passive"))
      (node (ref "C9") (pin "1") (pinfunction "1_1") (pintype "passive"))
      (node (ref "J1") (pin "5") (pinfunction "GND_5") (pintype "power_in"))
      (node (ref "J2") (pin "3") (pintype "passive"))
      (node (ref "J2") (pin "MP") (pintype "passive"))
      (node (ref "LED1") (pin "3") (pinfunction "VSS_3") (pintype "power_in"))
      (node (ref "LED2") (pin "3") (pinfunction "VSS_3") (pintype "power_in"))
      (node (ref "LED3") (pin "3") (pinfunction "VSS_3") (pintype "power_in"))
      (node (ref "LED4") (pin "3") (pinfunction "VSS_3") (pintype "power_in"))
      (node (ref "LED5") (pin "3") (pinfunction "VSS_3") (pintype "power_in"))
      (node (ref "LED6") (pin "3") (pinfunction "VSS_3") (pintype "power_in"))
      (node (ref "LED7") (pin "3") (pinfunction "VSS_3") (pintype "power_in"))
      (node (ref "M1") (pin "13") (pinfunction "GND_13") (pintype "power_in"))
      (node (ref "M1") (pin "18") (pinfunction "GND_18") (pintype "power_in"))
      (node (ref "M1") (pin "23") (pinfunction "GND_23") (pintype "power_in"))
      (node (ref "M1") (pin "28") (pinfunction "GND_28") (pintype "power_in"))
      (node (ref "M1") (pin "3") (pinfunction "GND_3") (pintype "power_in"))
      (node (ref "M1") (pin "33") (pinfunction "GND/AGND_33") (pintype "power_in"))
      (node (ref "M1") (pin "38") (pinfunction "GND_38") (pintype "power_in"))
      (node (ref "M1") (pin "42") (pinfunction "GND_42") (pintype "power_in"))
      (node (ref "M1") (pin "44") (pinfunction "TP1/GND_44") (pintype "bidirectional"))
      (node (ref "M1") (pin "8") (pinfunction "GND_8") (pintype "power_in"))
      (node (ref "R10") (pin "1") (pinfunction "1_1") (pintype "passive"))
      (node (ref "R27") (pin "2") (pinfunction "2_2") (pintype "passive"))
      (node (ref "R3") (pin "1") (pinfunction "1_1") (pintype "passive"))
      (node (ref "R30") (pin "1") (pinfunction "1_1") (pintype "passive"))
      (node (ref "R32") (pin "2") (pinfunction "2_2") (pintype "passive"))
      (node (ref "R8") (pin "1") (pinfunction "1_1") (pintype "passive"))
      (node (ref "SW1") (pin "1") (pinfunction "1_1") (pintype "passive"))
      (node (ref "SW1") (pin "2") (pinfunction "2_2") (pintype "passive"))
      (node (ref "SW2") (pin "1") (pinfunction "1_1") (pintype "passive"))
      (node (ref "SW2") (pin "2") (pinfunction "2_2") (pintype "passive"))
      (node (ref "U1") (pin "2") (pinfunction "VCC-_2") (pintype "power_in"))
      (node (ref "U2") (pin "3") (pinfunction "GND_3") (pintype "power_in"))
      (node (ref "U2") (pin "EP") (pinfunction "GND_EP") (pintype "power_in"))
      (node (ref "U3") (pin "2") (pinfunction "VSS_2") (pintype "power_in"))
      (node (ref "U3") (pin "6") (pinfunction "A0_6") (pintype "input"))
      (node (ref "U4") (pin "3") (pinfunction "GND_3") (pintype "power_in"))
      (node (ref "U5") (pin "3") (pinfunction "GND_3") (pintype "passive"))
      (node (ref "U5") (pin "7") (pinfunction "A0_7") (pintype "input"))
      (node (ref "U5") (pin "8") (pinfunction "A1_8") (pintype "input"))
      (node (ref "U6") (pin "2") (pinfunction "GND_2") (pintype "power_in"))
      (node (ref "U7") (pin "2") (pinfunction "VCC-_2") (pintype "power_in"))
      (node (ref "U8") (pin "10") (pinfunction "RES_10") (pintype "power_in"))
      (node (ref "U8") (pin "12") (pinfunction "GND_12") (pintype "power_in"))
      (node (ref "U8") (pin "5") (pinfunction "GND_5") (pintype "power_in"))
      (node (ref "U9") (pin "2") (pinfunction "PGND_2") (pintype "power_in"))
      (node (ref "U9") (pin "4") (pinfunction "AGND_4") (pintype "power_in"))
      (node (ref "U9") (pin "7") (pinfunction "~{PG}_7") (pintype "open_collector"))
      (node (ref "U9") (pin "EP") (pinfunction "AGND_EP") (pintype "power_in"))
    )
    (net (code "21") (name "Net-(C1-Pad2)") (class "Default")
      (node (ref "C1") (pin "2") (pinfunction "2_2") (pintype "passive"))
      (node (ref "R1") (pin "1") (pinfunction "1_1") (pintype "passive"))
    )
    (net (code "22") (name "Net-(C2-Pad2)") (class "Default")
      (node (ref "C2") (pin "2") (pinfunction "2_2") (pintype "passive"))
      (node (ref "R2") (pin "1") (pinfunction "1_1") (pintype "passive"))
    )
    (net (code "23") (name "Net-(C13-Pad2)") (class "Default")
      (node (ref "C13") (pin "2") (pinfunction "2_2") (pintype "passive"))
      (node (ref "R19") (pin "2") (pinfunction "2_2") (pintype "passive"))
    )
    (net (code "24") (name "Net-(J1-SWDIO)") (class "Default")
      (node (ref "J1") (pin "2") (pinfunction "SWDIO_2") (pintype "bidirectional"))
      (node (ref "M1") (pin "41") (pinfunction "SWCLK_41") (pintype "bidirectional"))
    )
    (net (code "25") (name "Net-(J1-SWO)") (class "Default")
      (node (ref "J1") (pin "6") (pinfunction "SWO_6") (pintype "bidirectional"))
      (node (ref "M1") (pin "43") (pinfunction "SWDIO_43") (pintype "bidirectional"))
    )
    (net (code "26") (name "Net-(LED1-DIN)") (class "Default")
      (node (ref "LED1") (pin "4") (pinfunction "DIN_4") (pintype "input"))
      (node (ref "R9") (pin "2") (pinfunction "2_2") (pintype "passive"))
    )
    (net (code "27") (name "Net-(LED1-DOUT)") (class "Default")
      (node (ref "LED1") (pin "1") (pinfunction "DOUT_1") (pintype "output"))
      (node (ref "LED2") (pin "4") (pinfunction "DIN_4") (pintype "input"))
    )
    (net (code "28") (name "Net-(LED2-DOUT)") (class "Default")
      (node (ref "LED2") (pin "1") (pinfunction "DOUT_1") (pintype "output"))
      (node (ref "LED5") (pin "4") (pinfunction "DIN_4") (pintype "input"))
    )
    (net (code "29") (name "Net-(LED3-DIN)") (class "Default")
      (node (ref "LED3") (pin "4") (pinfunction "DIN_4") (pintype "input"))
      (node (ref "LED5") (pin "1") (pinfunction "DOUT_1") (pintype "output"))
    )
    (net (code "30") (name "Net-(LED3-DOUT)") (class "Default")
      (node (ref "LED3") (pin "1") (pinfunction "DOUT_1") (pintype "output"))
      (node (ref "LED4") (pin "4") (pinfunction "DIN_4") (pintype "input"))
    )
    (net (code "31") (name "Net-(LED4-DOUT)") (class "Default")
      (node (ref "LED4") (pin "1") (pinfunction "DOUT_1") (pintype "output"))
      (node (ref "LED6") (pin "4") (pinfunction "DIN_4") (pintype "input"))
    )
    (net (code "32") (name "Net-(LED6-DOUT)") (class "Default")
      (node (ref "LED6") (pin "1") (pinfunction "DOUT_1") (pintype "output"))
      (node (ref "LED7") (pin "4") (pinfunction "DIN_4") (pintype "input"))
    )
    (net (code "33") (name "Net-(R12-Pad1)") (class "Default")
      (node (ref "R12") (pin "1") (pinfunction "1_1") (pintype "passive"))
      (node (ref "R14") (pin "2") (pinfunction "2_2") (pintype "passive"))
      (node (ref "R15") (pin "2") (pinfunction "2_2") (pintype "passive"))
    )
    (net (code "34") (name "Net-(R18-Pad1)") (class "Default")
      (node (ref "R18") (pin "1") (pinfunction "1_1") (pintype "passive"))
      (node (ref "R19") (pin "1") (pinfunction "1_1") (pintype "passive"))
    )
    (net (code "35") (name "Net-(R25-Pad2)") (class "Default")
      (node (ref "R25") (pin "2") (pinfunction "2_2") (pintype "passive"))
      (node (ref "R28") (pin "1") (pinfunction "1_1") (pintype "passive"))
    )
    (net (code "36") (name "Net-(R33-Pad2)") (class "Default")
      (node (ref "R33") (pin "2") (pinfunction "2_2") (pintype "passive"))
      (node (ref "R34") (pin "2") (pinfunction "2_2") (pintype "passive"))
    )
    (net (code "37") (name "Net-(R34-Pad1)") (class "Default")
      (node (ref "R34") (pin "1") (pinfunction "1_1") (pintype "passive"))
      (node (ref "R35") (pin "1") (pinfunction "1_1") (pintype "passive"))
    )
    (net (code "38") (name "Net-(R35-Pad2)") (class "Default")
      (node (ref "R35") (pin "2") (pinfunction "2_2") (pintype "passive"))
      (node (ref "R36") (pin "2") (pinfunction "2_2") (pintype "passive"))
    )
    (net (code "39") (name "Net-(U1-1IN+)") (class "Default")
      (node (ref "R16") (pin "1") (pinfunction "1_1") (pintype "passive"))
      (node (ref "R17") (pin "1") (pinfunction "1_1") (pintype "passive"))
      (node (ref "R20") (pin "1") (pinfunction "1_1") (pintype "passive"))
      (node (ref "U1") (pin "1") (pinfunction "1IN+_1") (pintype "input"))
    )
    (net (code "40") (name "Net-(U1-1IN-)") (class "Default")
      (node (ref "C17") (pin "1") (pinfunction "1_1") (pintype "passive"))
      (node (ref "R14") (pin "1") (pinfunction "1_1") (pintype "passive"))
      (node (ref "R15") (pin "1") (pinfunction "1_1") (pintype "passive"))
      (node (ref "R21") (pin "1") (pinfunction "1_1") (pintype "passive"))
      (node (ref "U1") (pin "8") (pinfunction "1IN-_8") (pintype "input"))
    )
    (net (code "41") (name "Net-(U1-1OUT)") (class "Default")
      (node (ref "C17") (pin "2") (pinfunction "2_2") (pintype "passive"))
      (node (ref "R21") (pin "2") (pinfunction "2_2") (pintype "passive"))
      (node (ref "R25") (pin "1") (pinfunction "1_1") (pintype "passive"))
      (node (ref "U1") (pin "7") (pinfunction "1OUT_7") (pintype "output"))
    )
    (net (code "42") (name "Net-(U1-2IN-)") (class "Default")
      (node (ref "R20") (pin "2") (pinfunction "2_2") (pintype "passive"))
      (node (ref "R26") (pin "1") (pinfunction "1_1") (pintype "passive"))
      (node (ref "U1") (pin "4") (pinfunction "2IN-_4") (pintype "input"))
      (node (ref "U1") (pin "5") (pinfunction "2OUT_5") (pintype "output"))
    )
    (net (code "43") (name "Net-(U2-PROG)") (class "Default")
      (node (ref "R3") (pin "2") (pinfunction "2_2") (pintype "passive"))
      (node (ref "U2") (pin "2") (pinfunction "PROG_2") (pintype "input"))
    )
    (net (code "44") (name "Net-(U2-TEMP)") (class "Default")
      (node (ref "R6") (pin "2") (pinfunction "2_2") (pintype "passive"))
      (node (ref "R7") (pin "2") (pinfunction "2_2") (pintype "passive"))
      (node (ref "R8") (pin "2") (pinfunction "2_2") (pintype "passive"))
      (node (ref "U2") (pin "1") (pinfunction "TEMP_1") (pintype "input"))
    )
    (net (code "45") (name "Net-(U4-VIN)") (class "Default")
      (node (ref "C14") (pin "2") (pinfunction "2_2") (pintype "passive"))
      (node (ref "C9") (pin "2") (pinfunction "2_2") (pintype "passive"))
      (node (ref "R11") (pin "1") (pinfunction "1_1") (pintype "passive"))
      (node (ref "U4") (pin "1") (pinfunction "VIN_1") (pintype "power_in"))
    )
    (net (code "46") (name "Net-(U5-IN-)") (class "Default")
      (node (ref "J3") (pin "R") (pinfunction "R_R") (pintype "passive"))
      (node (ref "R29") (pin "2") (pinfunction "2_2") (pintype "passive"))
      (node (ref "U5") (pin "2") (pinfunction "IN-_2") (pintype "input"))
    )
    (net (code "47") (name "Net-(U5-Vs)") (class "Default")
      (node (ref "C18") (pin "2") (pinfunction "2_2") (pintype "passive"))
      (node (ref "C20") (pin "2") (pinfunction "2_2") (pintype "passive"))
      (node (ref "R24") (pin "1") (pinfunction "1_1") (pintype "passive"))
      (node (ref "U5") (pin "4") (pinfunction "Vs_4") (pintype "passive"))
    )
    (net (code "48") (name "Net-(U6-FB)") (class "Default")
      (node (ref "R30") (pin "2") (pinfunction "2_2") (pintype "passive"))
      (node (ref "R36") (pin "1") (pinfunction "1_1") (pintype "passive"))
      (node (ref "U6") (pin "3") (pinfunction "FB_3") (pintype "input"))
    )
    (net (code "49") (name "Net-(U6-SW)") (class "Default")
      (node (ref "D3") (pin "A") (pinfunction "A_A") (pintype "passive"))
      (node (ref "L1") (pin "2") (pinfunction "2_2") (pintype "passive"))
      (node (ref "U6") (pin "1") (pinfunction "SW_1") (pintype "power_in"))
    )
    (net (code "50") (name "Net-(U7-1IN+)") (class "Default")
      (node (ref "R31") (pin "2") (pinfunction "2_2") (pintype "passive"))
      (node (ref "R32") (pin "1") (pinfunction "1_1") (pintype "passive"))
      (node (ref "U7") (pin "1") (pinfunction "1IN+_1") (pintype "input"))
      (node (ref "U7") (pin "3") (pinfunction "2IN+_3") (pintype "input"))
    )
    (net (code "51") (name "Net-(U7-1IN-)") (class "Default")
      (node (ref "C23") (pin "1") (pinfunction "1_1") (pintype "passive"))
      (node (ref "R26") (pin "2") (pinfunction "2_2") (pintype "passive"))
      (node (ref "R37") (pin "1") (pinfunction "1_1") (pintype "passive"))
      (node (ref "U7") (pin "8") (pinfunction "1IN-_8") (pintype "input"))
    )
    (net (code "52") (name "Net-(U7-2IN-)") (class "Default")
      (node (ref "U7") (pin "4") (pinfunction "2IN-_4") (pintype "input"))
      (node (ref "U7") (pin "5") (pinfunction "2OUT_5") (pintype "output"))
    )
    (net (code "53") (name "Net-(U9-SW)") (class "Default")
      (node (ref "L2") (pin "2") (pinfunction "2_2") (pintype "passive"))
      (node (ref "U9") (pin "1") (pinfunction "SW_1") (pintype "power_in"))
    )
    (net (code "54") (name "VBAT") (class "Default")
      (node (ref "J2") (pin "1") (pintype "passive"))
      (node (ref "Q1") (pin "3") (pinfunction "D_3") (pintype "power_in"))
      (node (ref "R1") (pin "2") (pinfunction "2_2") (pintype "passive"))
      (node (ref "U2") (pin "5") (pinfunction "BAT_5") (pintype "power_in"))
    )
    (net (code "55") (name "VBUS") (class "Default")
      (node (ref "D1") (pin "A") (pinfunction "A_A") (pintype "passive"))
      (node (ref "M1") (pin "40") (pinfunction "VBUS_40") (pintype "power_in"))
      (node (ref "Q1") (pin "1") (pinfunction "G_1") (pintype "power_in"))
      (node (ref "R10") (pin "2") (pinfunction "2_2") (pintype "passive"))
      (node (ref "R2") (pin "2") (pinfunction "2_2") (pintype "passive"))
      (node (ref "R6") (pin "1") (pinfunction "1_1") (pintype "passive"))
      (node (ref "U2") (pin "4") (pinfunction "VCC_4") (pintype "power_in"))
      (node (ref "U2") (pin "8") (pinfunction "CE_8") (pintype "input"))
    )
    (net (code "56") (name "VSYS") (class "Default")
      (node (ref "C15") (pin "2") (pinfunction "2_2") (pintype "passive"))
      (node (ref "C19") (pin "2") (pinfunction "2_2") (pintype "passive"))
      (node (ref "C21") (pin "2") (pinfunction "2_2") (pintype "passive"))
      (node (ref "C28") (pin "2") (pinfunction "2_2") (pintype "passive"))
      (node (ref "C3") (pin "2") (pinfunction "2_2") (pintype "passive"))
      (node (ref "C4") (pin "2") (pinfunction "2_2") (pintype "passive"))
      (node (ref "C5") (pin "2") (pinfunction "2_2") (pintype "passive"))
      (node (ref "C6") (pin "2") (pinfunction "2_2") (pintype "passive"))
      (node (ref "C7") (pin "2") (pinfunction "2_2") (pintype "passive"))
      (node (ref "C8") (pin "2") (pinfunction "2_2") (pintype "passive"))
      (node (ref "D1") (pin "K") (pinfunction "K_K") (pintype "passive"))
      (node (ref "L1") (pin "1") (pinfunction "1_1") (pintype "passive"))
      (node (ref "L2") (pin "1") (pinfunction "1_1") (pintype "passive"))
      (node (ref "LED1") (pin "2") (pinfunction "VDD_2") (pintype "power_in"))
      (node (ref "LED2") (pin "2") (pinfunction "VDD_2") (pintype "power_in"))
      (node (ref "LED3") (pin "2") (pinfunction "VDD_2") (pintype "power_in"))
      (node (ref "LED4") (pin "2") (pinfunction "VDD_2") (pintype "power_in"))
      (node (ref "LED5") (pin "2") (pinfunction "VDD_2") (pintype "power_in"))
      (node (ref "LED6") (pin "2") (pinfunction "VDD_2") (pintype "power_in"))
      (node (ref "LED7") (pin "2") (pinfunction "VDD_2") (pintype "power_in"))
      (node (ref "M1") (pin "39") (pinfunction "VSYS_39") (pintype "power_in"))
      (node (ref "Q1") (pin "2") (pinfunction "S_2") (pintype "power_in"))
      (node (ref "U6") (pin "5") (pinfunction "VIN_5") (pintype "power_in"))
      (node (ref "U9") (pin "3") (pinfunction "IN_3") (pintype "power_in"))
    )
    (net (code "57") (name "unconnected-(J1-SWCLK-Pad4)") (class "Default")
      (node (ref "J1") (pin "4") (pinfunction "SWCLK_4") (pintype "bidirectional+no_connect"))
    )
    (net (code "58") (name "unconnected-(J1-VCC-Pad1)") (class "Default")
      (node (ref "J1") (pin "1") (pinfunction "VCC_1") (pintype "power_in+no_connect"))
    )
    (net (code "59") (name "unconnected-(J1-nRST-Pad3)") (class "Default")
      (node (ref "J1") (pin "3") (pinfunction "nRST_3") (pintype "bidirectional+no_connect"))
    )
    (net (code "60") (name "unconnected-(J3-PadS)") (class "Default")
      (node (ref "J3") (pin "S") (pinfunction "S_S") (pintype "passive+no_connect"))
    )
    (net (code "61") (name "unconnected-(LED7-DOUT-Pad1)") (class "Default")
      (node (ref "LED7") (pin "1") (pinfunction "DOUT_1") (pintype "output+no_connect"))
    )
    (net (code "62") (name "unconnected-(M1-3V3_EN-Pad37)") (class "Default")
      (node (ref "M1") (pin "37") (pinfunction "3V3_EN_37") (pintype "input+no_connect"))
    )
    (net (code "63") (name "unconnected-(M1-ADC_VREF-Pad35)") (class "Default")
      (node (ref "M1") (pin "35") (pinfunction "ADC_VREF_35") (pintype "power_in+no_connect"))
    )
    (net (code "64") (name "unconnected-(M1-GP0{slash}SPI0_RX{slash}I2C0_SDA{slash}UART0_TX-Pad1)") (class "Default")
      (node (ref "M1") (pin "1") (pinfunction "GP0/SPI0_RX/I2C0_SDA/UART0_TX_1") (pintype "bidirectional+no_connect"))
    )
    (net (code "65") (name "unconnected-(M1-GP1{slash}SPI0_CSn{slash}I2C0_SCL{slash}UART0_RX-Pad2)") (class "Default")
      (node (ref "M1") (pin "2") (pinfunction "GP1/SPI0_CSn/I2C0_SCL/UART0_RX_2") (pintype "bidirectional+no_connect"))
    )
    (net (code "66") (name "unconnected-(M1-GP2{slash}SPI0_SCK{slash}I2C1_SDA-Pad4)") (class "Default")
      (node (ref "M1") (pin "4") (pinfunction "GP2/SPI0_SCK/I2C1_SDA_4") (pintype "bidirectional+no_connect"))
    )
    (net (code "67") (name "unconnected-(M1-GP4{slash}SPI0_RX{slash}I2C0_SDA{slash}UART1_TX-Pad6)") (class "Default")
      (node (ref "M1") (pin "6") (pinfunction "GP4/SPI0_RX/I2C0_SDA/UART1_TX_6") (pintype "bidirectional+no_connect"))
    )
    (net (code "68") (name "unconnected-(M1-GP5{slash}SPI0_CSn{slash}I2C0_SCL{slash}UART1_RX-Pad7)") (class "Default")
      (node (ref "M1") (pin "7") (pinfunction "GP5/SPI0_CSn/I2C0_SCL/UART1_RX_7") (pintype "bidirectional+no_connect"))
    )
    (net (code "69") (name "unconnected-(M1-GP6{slash}SPI0_SCK{slash}I2C1_SDA-Pad9)") (class "Default")
      (node (ref "M1") (pin "9") (pinfunction "GP6/SPI0_SCK/I2C1_SDA_9") (pintype "bidirectional+no_connect"))
    )
    (net (code "70") (name "unconnected-(M1-GP7{slash}SPI0_TX{slash}I2C1_SCL-Pad10)") (class "Default")
      (node (ref "M1") (pin "10") (pinfunction "GP7/SPI0_TX/I2C1_SCL_10") (pintype "bidirectional+no_connect"))
    )
    (net (code "71") (name "unconnected-(M1-GP8{slash}SPI1_RX{slash}I2C0_SDA{slash}UART1_TX-Pad11)") (class "Default")
      (node (ref "M1") (pin "11") (pinfunction "GP8/SPI1_RX/I2C0_SDA/UART1_TX_11") (pintype "bidirectional+no_connect"))
    )
    (net (code "72") (name "unconnected-(M1-GP9{slash}SPI1_CSn{slash}I2C0_SCL{slash}UART1_RX-Pad12)") (class "Default")
      (node (ref "M1") (pin "12") (pinfunction "GP9/SPI1_CSn/I2C0_SCL/UART1_RX_12") (pintype "bidirectional+no_connect"))
    )
    (net (code "73") (name "unconnected-(M1-GP10{slash}SPI1_SCK{slash}I2C1_SDA-Pad14)") (class "Default")
      (node (ref "M1") (pin "14") (pinfunction "GP10/SPI1_SCK/I2C1_SDA_14") (pintype "bidirectional+no_connect"))
    )
    (net (code "74") (name "unconnected-(M1-GP11{slash}SPI1_TX{slash}I2C1_SCL-Pad15)") (class "Default")
      (node (ref "M1") (pin "15") (pinfunction "GP11/SPI1_TX/I2C1_SCL_15") (pintype "bidirectional+no_connect"))
    )
    (net (code "75") (name "unconnected-(M1-GP12{slash}SPI1_RX{slash}I2C0_SDA{slash}UART0_TX-Pad16)") (class "Default")
      (node (ref "M1") (pin "16") (pinfunction "GP12/SPI1_RX/I2C0_SDA/UART0_TX_16") (pintype "bidirectional+no_connect"))
    )
    (net (code "76") (name "unconnected-(M1-GP17{slash}SPI0_CSn{slash}I2C0_SCL{slash}UART0_RX-Pad22)") (class "Default")
      (node (ref "M1") (pin "22") (pinfunction "GP17/SPI0_CSn/I2C0_SCL/UART0_RX_22") (pintype "bidirectional+no_connect"))
    )
    (net (code "77") (name "unconnected-(M1-GP18{slash}SPI0_SCK{slash}I2C1_SDA-Pad24)") (class "Default")
      (node (ref "M1") (pin "24") (pinfunction "GP18/SPI0_SCK/I2C1_SDA_24") (pintype "bidirectional+no_connect"))
    )
    (net (code "78") (name "unconnected-(M1-GP19{slash}SPI0_TX{slash}I2C1_SCL-Pad25)") (class "Default")
      (node (ref "M1") (pin "25") (pinfunction "GP19/SPI0_TX/I2C1_SCL_25") (pintype "bidirectional+no_connect"))
    )
    (net (code "79") (name "unconnected-(M1-RUN-Pad30)") (class "Default")
      (node (ref "M1") (pin "30") (pinfunction "RUN_30") (pintype "input+no_connect"))
    )
    (net (code "80") (name "unconnected-(M1-TP2{slash}USB_DM-Pad45)") (class "Default")
      (node (ref "M1") (pin "45") (pinfunction "TP2/USB_DM_45") (pintype "bidirectional+no_connect"))
    )
    (net (code "81") (name "unconnected-(M1-TP3{slash}USB_DP-Pad46)") (class "Default")
      (node (ref "M1") (pin "46") (pinfunction "TP3/USB_DP_46") (pintype "bidirectional+no_connect"))
    )
    (net (code "82") (name "unconnected-(M1-TP4{slash}SMPS_PS-Pad47)") (class "Default")
      (node (ref "M1") (pin "47") (pinfunction "TP4/SMPS_PS_47") (pintype "bidirectional+no_connect"))
    )
    (net (code "83") (name "unconnected-(M1-TP5{slash}LED-Pad48)") (class "Default")
      (node (ref "M1") (pin "48") (pinfunction "TP5/LED_48") (pintype "bidirectional+no_connect"))
    )
    (net (code "84") (name "unconnected-(M1-TP6{slash}BOOTSEL-Pad49)") (class "Default")
      (node (ref "M1") (pin "49") (pinfunction "TP6/BOOTSEL_49") (pintype "bidirectional+no_connect"))
    )
    (net (code "85") (name "unconnected-(U6-NC-Pad6)") (class "Default")
      (node (ref "U6") (pin "6") (pinfunction "NC_6") (pintype "passive+no_connect"))
    )
    (net (code "86") (name "unconnected-(U8-ADC1-Pad16)") (class "Default")
      (node (ref "U8") (pin "16") (pinfunction "ADC1_16") (pintype "input+no_connect"))
    )
    (net (code "87") (name "unconnected-(U8-ADC2-Pad15)") (class "Default")
      (node (ref "U8") (pin "15") (pinfunction "ADC2_15") (pintype "input+no_connect"))
    )
    (net (code "88") (name "unconnected-(U8-ADC3-Pad13)") (class "Default")
      (node (ref "U8") (pin "13") (pinfunction "ADC3_13") (pintype "input+no_connect"))
    )
    (net (code "89") (name "unconnected-(U8-INT1-Pad11)") (class "Default")
      (node (ref "U8") (pin "11") (pinfunction "INT1_11") (pintype "output+no_connect"))
    )
    (net (code "90") (name "unconnected-(U8-INT2-Pad9)") (class "Default")
      (node (ref "U8") (pin "9") (pinfunction "INT2_9") (pintype "output+no_connect"))
    )
    (net (code "91") (name "unconnected-(U8-NC-Pad2)") (class "Default")
      (node (ref "U8") (pin "2") (pinfunction "NC_2") (pintype "power_in+no_connect"))
    )
    (net (code "92") (name "unconnected-(U8-NC-Pad3)") (class "Default")
      (node (ref "U8") (pin "3") (pinfunction "NC_3") (pintype "power_in+no_connect"))
    )
  )
)
